# bno08x_module.net
KiCad netlist of a schematic drawn in Altium Designer
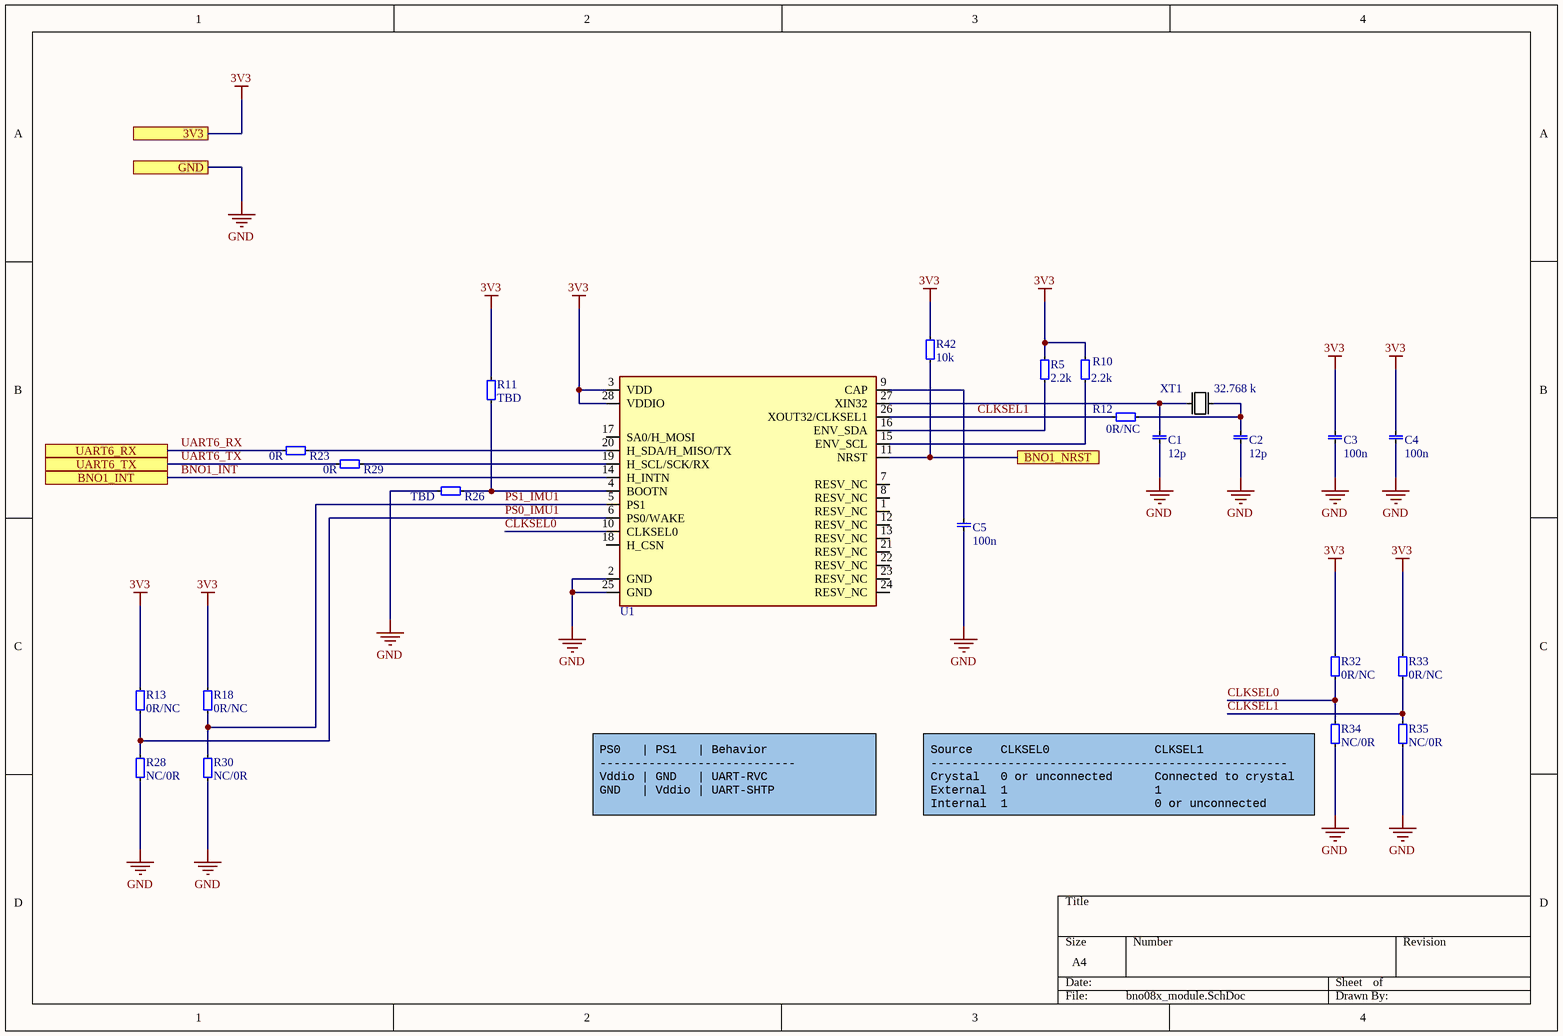
[diagram p0: bno08x_module.SchDoc]

(export (version "E")
  (design (tool "Eeschema 10.0.6"))
  (components
    (comp (ref "C1")
      (value "12p")
      (footprint "0402 CAP")
      (fields
        (field (name "MANUFACTURER PART NO") "GJM1555C1H120JB01D")
        (field (name "Comment") "0402 capacitor")
      )
      (libsource (lib "jclib") (part "0402 capacitor"))
    )
    (comp (ref "C2")
      (value "12p")
      (footprint "0402 CAP")
      (fields
        (field (name "MANUFACTURER PART NO") "GJM1555C1H120JB01D")
        (field (name "Comment") "0402 capacitor")
      )
      (libsource (lib "jclib") (part "0402 capacitor"))
    )
    (comp (ref "C3")
      (value "100n")
      (footprint "0402 CAP")
      (fields
        (field (name "MANUFACTURER PART NO") "GRM155R62A104KE14D")
        (field (name "Comment") "0402 capacitor")
      )
      (libsource (lib "jclib") (part "0402 capacitor"))
    )
    (comp (ref "C4")
      (value "100n")
      (footprint "0402 CAP")
      (fields
        (field (name "MANUFACTURER PART NO") "GRM155R62A104KE14D")
        (field (name "Comment") "0402 capacitor")
      )
      (libsource (lib "jclib") (part "0402 capacitor"))
    )
    (comp (ref "C5")
      (value "100n")
      (footprint "0402 CAP")
      (fields
        (field (name "MANUFACTURER PART NO") "GRM155R62A104KE14D")
        (field (name "Comment") "0402 capacitor")
      )
      (libsource (lib "jclib") (part "0402 capacitor"))
    )
    (comp (ref "R5")
      (value "2.2k")
      (footprint "0402 res")
      (fields
        (field (name "MANUFACTURER PART NO") "RC0402FR-072K2L")
        (field (name "Comment") "0402, resistor")
      )
      (libsource (lib "jclib") (part "0402, resistor"))
    )
    (comp (ref "R10")
      (value "2.2k")
      (footprint "0402 res")
      (fields
        (field (name "MANUFACTURER PART NO") "RC0402FR-072K2L")
        (field (name "Comment") "0402, resistor")
      )
      (libsource (lib "jclib") (part "0402, resistor"))
    )
    (comp (ref "R11")
      (value "TBD")
      (footprint "0402 res")
      (fields (field (name "Comment") "0402, resistor"))
      (libsource (lib "jclib") (part "0402, resistor"))
    )
    (comp (ref "R12")
      (value "0R/NC")
      (footprint "0402 res")
      (fields
        (field (name "MANUFACTURER PART NO") "RMCF0402ZT0R00")
        (field (name "Comment") "0402, resistor")
      )
      (libsource (lib "jclib") (part "0402, resistor"))
    )
    (comp (ref "R13")
      (value "0R/NC")
      (footprint "0402 res")
      (fields
        (field (name "MANUFACTURER PART NO") "RMCF0402ZT0R00")
        (field (name "Comment") "0402, resistor")
      )
      (libsource (lib "jclib") (part "0402, resistor"))
    )
    (comp (ref "R18")
      (value "0R/NC")
      (footprint "0402 res")
      (fields
        (field (name "MANUFACTURER PART NO") "RMCF0402ZT0R00")
        (field (name "Comment") "0402, resistor")
      )
      (libsource (lib "jclib") (part "0402, resistor"))
    )
    (comp (ref "R23")
      (value "0R")
      (footprint "0402 res")
      (fields
        (field (name "MANUFACTURER PART NO") "RMCF0402ZT0R00")
        (field (name "Comment") "0402, resistor")
      )
      (libsource (lib "jclib") (part "0402, resistor"))
    )
    (comp (ref "R26")
      (value "TBD")
      (footprint "0402 res")
      (fields (field (name "Comment") "0402, resistor"))
      (libsource (lib "jclib") (part "0402, resistor"))
    )
    (comp (ref "R28")
      (value "NC/0R")
      (footprint "0402 res")
      (fields
        (field (name "MANUFACTURER PART NO") "RMCF0402ZT0R00")
        (field (name "Comment") "0402, resistor")
      )
      (libsource (lib "jclib") (part "0402, resistor"))
    )
    (comp (ref "R29")
      (value "0R")
      (footprint "0402 res")
      (fields
        (field (name "MANUFACTURER PART NO") "RMCF0402ZT0R00")
        (field (name "Comment") "0402, resistor")
      )
      (libsource (lib "jclib") (part "0402, resistor"))
    )
    (comp (ref "R30")
      (value "NC/0R")
      (footprint "0402 res")
      (fields
        (field (name "MANUFACTURER PART NO") "RMCF0402ZT0R00")
        (field (name "Comment") "0402, resistor")
      )
      (libsource (lib "jclib") (part "0402, resistor"))
    )
    (comp (ref "R32")
      (value "0R/NC")
      (footprint "0402 res")
      (fields
        (field (name "MANUFACTURER PART NO") "RMCF0402ZT0R00")
        (field (name "Comment") "0402, resistor")
      )
      (libsource (lib "jclib") (part "0402, resistor"))
    )
    (comp (ref "R33")
      (value "0R/NC")
      (footprint "0402 res")
      (fields
        (field (name "MANUFACTURER PART NO") "RMCF0402ZT0R00")
        (field (name "Comment") "0402, resistor")
      )
      (libsource (lib "jclib") (part "0402, resistor"))
    )
    (comp (ref "R34")
      (value "NC/0R")
      (footprint "0402 res")
      (fields
        (field (name "MANUFACTURER PART NO") "RMCF0402ZT0R00")
        (field (name "Comment") "0402, resistor")
      )
      (libsource (lib "jclib") (part "0402, resistor"))
    )
    (comp (ref "R35")
      (value "NC/0R")
      (footprint "0402 res")
      (fields
        (field (name "MANUFACTURER PART NO") "RMCF0402ZT0R00")
        (field (name "Comment") "0402, resistor")
      )
      (libsource (lib "jclib") (part "0402, resistor"))
    )
    (comp (ref "R42")
      (value "10k")
      (footprint "0402 res")
      (fields
        (field (name "MANUFACTURER PART NO") "311-10.0KLRCT-ND")
        (field (name "Comment") "0402, resistor")
      )
      (libsource (lib "jclib") (part "0402, resistor"))
    )
    (comp (ref "U1")
      (value "BNO08X")
      (footprint "LGA-28_2")
      (description "9-axis IMU")
      (fields (field (name "MANUFACTURER PART NO") "BNO085"))
      (libsource (lib "jclib") (part "BNO08X"))
    )
    (comp (ref "XT1")
      (value "32.768 k")
      (footprint "ECS-.327-12.5-39-TR")
      (fields
        (field (name "MANUFACTURER PART NO") "CC4V-T1A-32.768KHZ-9PF-20PPM-TA-QC")
        (field (name "Comment") "Crystal")
      )
      (libsource (lib "jclib") (part "Crystal"))
    )
  )
  (nets
    (net (code "1") (name "/BNO1_INT") (class "Default")
      (node (ref "U1") (pin "14") (pinfunction "H_INTN_14") (pintype "passive"))
    )
    (net (code "2") (name "/BNO1_NRST") (class "Default")
      (node (ref "R42") (pin "0") (pinfunction "0_0") (pintype "passive"))
      (node (ref "U1") (pin "11") (pinfunction "NRST_11") (pintype "passive"))
    )
    (net (code "3") (name "/CLKSEL0") (class "Default")
      (node (ref "R32") (pin "1") (pinfunction "1_1") (pintype "passive"))
      (node (ref "R34") (pin "0") (pinfunction "0_0") (pintype "passive"))
      (node (ref "U1") (pin "10") (pinfunction "CLKSEL0_10") (pintype "passive"))
    )
    (net (code "4") (name "/CLKSEL1") (class "Default")
      (node (ref "R12") (pin "0") (pinfunction "0_0") (pintype "passive"))
      (node (ref "R33") (pin "1") (pinfunction "1_1") (pintype "passive"))
      (node (ref "R35") (pin "0") (pinfunction "0_0") (pintype "passive"))
      (node (ref "U1") (pin "26") (pinfunction "XOUT32/CLKSEL1_26") (pintype "passive"))
    )
    (net (code "5") (name "/PS0_IMU1") (class "Default")
      (node (ref "R13") (pin "1") (pinfunction "1_1") (pintype "passive"))
      (node (ref "R28") (pin "0") (pinfunction "0_0") (pintype "passive"))
      (node (ref "U1") (pin "6") (pinfunction "PS0/WAKE_6") (pintype "passive"))
    )
    (net (code "6") (name "/PS1_IMU1") (class "Default")
      (node (ref "R18") (pin "1") (pinfunction "1_1") (pintype "passive"))
      (node (ref "R30") (pin "0") (pinfunction "0_0") (pintype "passive"))
      (node (ref "U1") (pin "5") (pinfunction "PS1_5") (pintype "passive"))
    )
    (net (code "7") (name "/UART6_RX") (class "Default")
      (node (ref "R23") (pin "1") (pinfunction "1_1") (pintype "passive"))
    )
    (net (code "8") (name "/UART6_TX") (class "Default")
      (node (ref "R29") (pin "1") (pinfunction "1_1") (pintype "passive"))
    )
    (net (code "9") (name "3V3") (class "Default")
      (node (ref "C3") (pin "1") (pinfunction "1_1") (pintype "passive"))
      (node (ref "C4") (pin "1") (pinfunction "1_1") (pintype "passive"))
      (node (ref "R10") (pin "1") (pinfunction "1_1") (pintype "passive"))
      (node (ref "R11") (pin "1") (pinfunction "1_1") (pintype "passive"))
      (node (ref "R13") (pin "0") (pinfunction "0_0") (pintype "passive"))
      (node (ref "R18") (pin "0") (pinfunction "0_0") (pintype "passive"))
      (node (ref "R32") (pin "0") (pinfunction "0_0") (pintype "passive"))
      (node (ref "R33") (pin "0") (pinfunction "0_0") (pintype "passive"))
      (node (ref "R42") (pin "1") (pinfunction "1_1") (pintype "passive"))
      (node (ref "R5") (pin "1") (pinfunction "1_1") (pintype "passive"))
      (node (ref "U1") (pin "28") (pinfunction "VDDIO_28") (pintype "passive"))
      (node (ref "U1") (pin "3") (pinfunction "VDD_3") (pintype "passive"))
    )
    (net (code "10") (name "GND") (class "Default")
      (node (ref "C1") (pin "0") (pinfunction "0_0") (pintype "passive"))
      (node (ref "C2") (pin "0") (pinfunction "0_0") (pintype "passive"))
      (node (ref "C3") (pin "0") (pinfunction "0_0") (pintype "passive"))
      (node (ref "C4") (pin "0") (pinfunction "0_0") (pintype "passive"))
      (node (ref "C5") (pin "0") (pinfunction "0_0") (pintype "passive"))
      (node (ref "R26") (pin "1") (pinfunction "1_1") (pintype "passive"))
      (node (ref "R28") (pin "1") (pinfunction "1_1") (pintype "passive"))
      (node (ref "R30") (pin "1") (pinfunction "1_1") (pintype "passive"))
      (node (ref "R34") (pin "1") (pinfunction "1_1") (pintype "passive"))
      (node (ref "R35") (pin "1") (pinfunction "1_1") (pintype "passive"))
      (node (ref "U1") (pin "2") (pinfunction "GND_2") (pintype "passive"))
      (node (ref "U1") (pin "25") (pinfunction "GND_25") (pintype "passive"))
    )
    (net (code "11") (name "Net-(C2-Pad1)") (class "Default")
      (node (ref "C2") (pin "1") (pinfunction "1_1") (pintype "passive"))
      (node (ref "R12") (pin "1") (pinfunction "1_1") (pintype "passive"))
      (node (ref "XT1") (pin "2") (pinfunction "2_2") (pintype "passive"))
    )
    (net (code "12") (name "Net-(U1-BOOTN)") (class "Default")
      (node (ref "R11") (pin "0") (pinfunction "0_0") (pintype "passive"))
      (node (ref "R26") (pin "0") (pinfunction "0_0") (pintype "passive"))
      (node (ref "U1") (pin "4") (pinfunction "BOOTN_4") (pintype "passive"))
    )
    (net (code "13") (name "Net-(U1-CAP)") (class "Default")
      (node (ref "C5") (pin "1") (pinfunction "1_1") (pintype "passive"))
      (node (ref "U1") (pin "9") (pinfunction "CAP_9") (pintype "passive"))
    )
    (net (code "14") (name "Net-(U1-ENV_SCL)") (class "Default")
      (node (ref "R10") (pin "0") (pinfunction "0_0") (pintype "passive"))
      (node (ref "U1") (pin "15") (pinfunction "ENV_SCL_15") (pintype "passive"))
    )
    (net (code "15") (name "Net-(U1-ENV_SDA)") (class "Default")
      (node (ref "R5") (pin "0") (pinfunction "0_0") (pintype "passive"))
      (node (ref "U1") (pin "16") (pinfunction "ENV_SDA_16") (pintype "passive"))
    )
    (net (code "16") (name "Net-(U1-H_SCL{slash}SCK{slash}RX)") (class "Default")
      (node (ref "R29") (pin "0") (pinfunction "0_0") (pintype "passive"))
      (node (ref "U1") (pin "19") (pinfunction "H_SCL/SCK/RX_19") (pintype "passive"))
    )
    (net (code "17") (name "Net-(U1-H_SDA{slash}H_MISO{slash}TX)") (class "Default")
      (node (ref "R23") (pin "0") (pinfunction "0_0") (pintype "passive"))
      (node (ref "U1") (pin "20") (pinfunction "H_SDA/H_MISO/TX_20") (pintype "passive"))
    )
    (net (code "18") (name "Net-(U1-XIN32)") (class "Default")
      (node (ref "C1") (pin "1") (pinfunction "1_1") (pintype "passive"))
      (node (ref "U1") (pin "27") (pinfunction "XIN32_27") (pintype "passive"))
      (node (ref "XT1") (pin "1") (pinfunction "1_1") (pintype "passive"))
    )
    (net (code "19") (name "unconnected-(U1-H_CSN-Pad18)") (class "Default")
      (node (ref "U1") (pin "18") (pinfunction "H_CSN_18") (pintype "passive"))
    )
    (net (code "20") (name "unconnected-(U1-RESV_NC-Pad1)") (class "Default")
      (node (ref "U1") (pin "1") (pinfunction "RESV_NC_1") (pintype "passive"))
    )
    (net (code "21") (name "unconnected-(U1-RESV_NC-Pad7)") (class "Default")
      (node (ref "U1") (pin "7") (pinfunction "RESV_NC_7") (pintype "passive"))
    )
    (net (code "22") (name "unconnected-(U1-RESV_NC-Pad8)") (class "Default")
      (node (ref "U1") (pin "8") (pinfunction "RESV_NC_8") (pintype "passive"))
    )
    (net (code "23") (name "unconnected-(U1-RESV_NC-Pad12)") (class "Default")
      (node (ref "U1") (pin "12") (pinfunction "RESV_NC_12") (pintype "passive"))
    )
    (net (code "24") (name "unconnected-(U1-RESV_NC-Pad13)") (class "Default")
      (node (ref "U1") (pin "13") (pinfunction "RESV_NC_13") (pintype "passive"))
    )
    (net (code "25") (name "unconnected-(U1-RESV_NC-Pad21)") (class "Default")
      (node (ref "U1") (pin "21") (pinfunction "RESV_NC_21") (pintype "passive"))
    )
    (net (code "26") (name "unconnected-(U1-RESV_NC-Pad22)") (class "Default")
      (node (ref "U1") (pin "22") (pinfunction "RESV_NC_22") (pintype "passive"))
    )
    (net (code "27") (name "unconnected-(U1-RESV_NC-Pad23)") (class "Default")
      (node (ref "U1") (pin "23") (pinfunction "RESV_NC_23") (pintype "passive"))
    )
    (net (code "28") (name "unconnected-(U1-RESV_NC-Pad24)") (class "Default")
      (node (ref "U1") (pin "24") (pinfunction "RESV_NC_24") (pintype "passive"))
    )
    (net (code "29") (name "unconnected-(U1-SA0{slash}H_MOSI-Pad17)") (class "Default")
      (node (ref "U1") (pin "17") (pinfunction "SA0/H_MOSI_17") (pintype "passive"))
    )
  )
)
